# SCH.net
KiCad netlist of a schematic drawn in Altium Designer
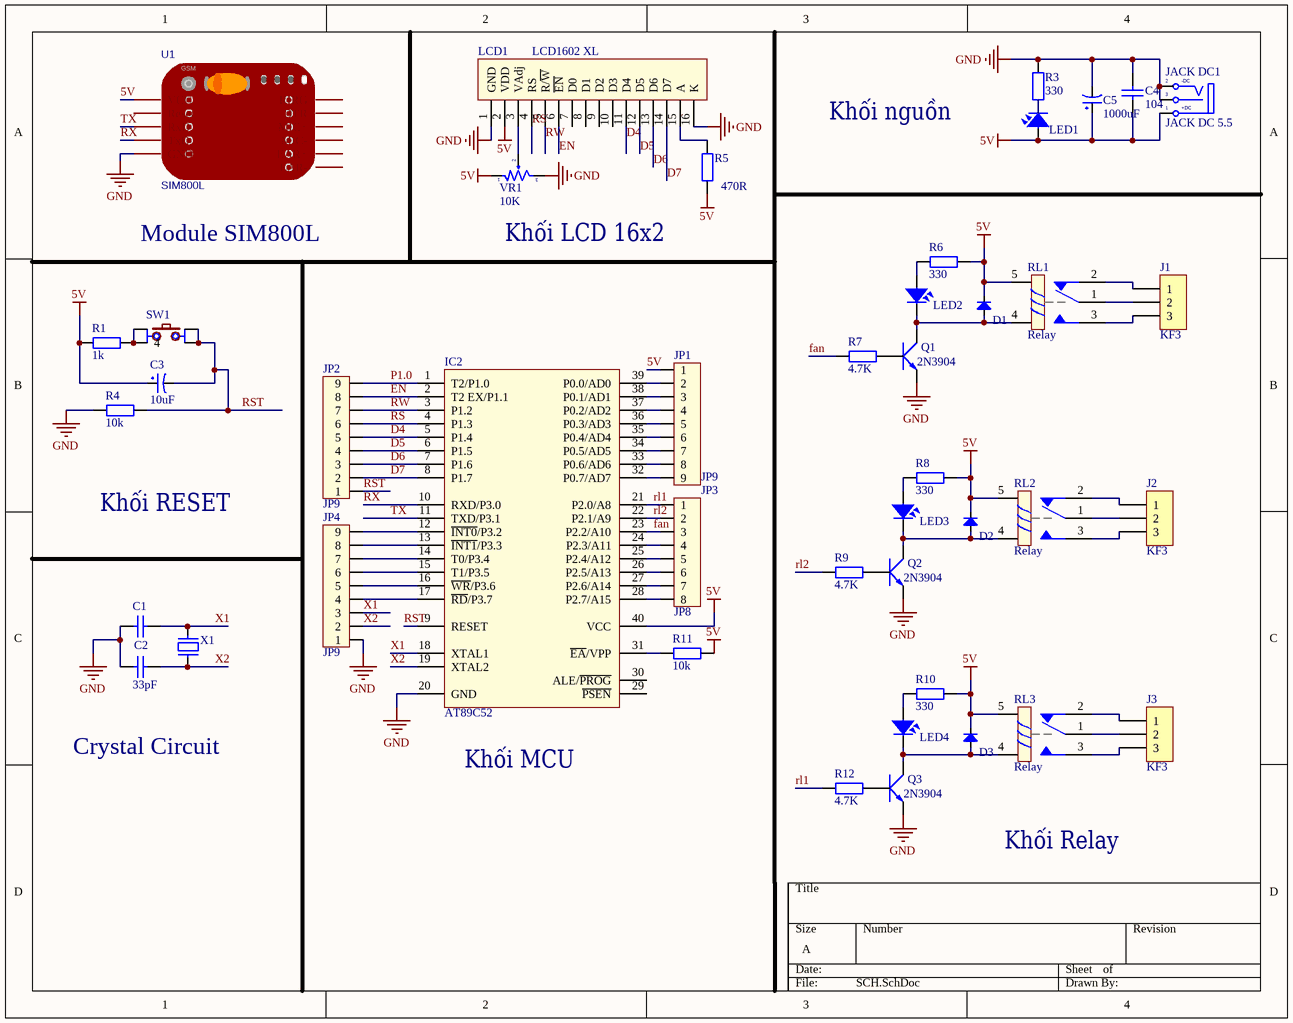
[diagram p0: SCH.SchDoc]

(export (version "E")
  (design (tool "Eeschema 10.0.6"))
  (components
    (comp (ref "C1")
      (value "30pF")
      (footprint "tu gom")
      (description "Cắm")
      (libsource (lib "Altium_Lib_by_KhueNguyenCreator") (part "Tu gom 30pF 50V"))
    )
    (comp (ref "C2")
      (value "33pF")
      (footprint "tu gom")
      (description "Cắm")
      (libsource (lib "Altium_Lib_by_KhueNguyenCreator") (part "Tu gom 30pF 50V"))
    )
    (comp (ref "C3")
      (value "10uF")
      (footprint "tu hoa 4mm")
      (description "Cắm")
      (libsource (lib "Altium_Lib_by_KhueNguyenCreator") (part "Tu Hoa 10uF 16V 4x7"))
    )
    (comp (ref "C4")
      (value "104")
      (footprint "tu gom")
      (description "Cắm")
      (libsource (lib "Altium_Lib_by_KhueNguyenCreator") (part "Tu gom 104 50V"))
    )
    (comp (ref "C5")
      (value "1000uF")
      (footprint "tu hoa 10mm")
      (description "Cắm")
      (libsource (lib "Altium_Lib_by_KhueNguyenCreator") (part "Tu Hoa 1000uF 10V 10x12"))
    )
    (comp (ref "D1")
      (value "Diode")
      (footprint "DIO-1A")
      (description "Default Diode")
      (fields (field (name "PUBLISHER") "Altium Limited"))
      (libsource (lib "TechMT.VN_Lib_Project v2") (part "Diode"))
    )
    (comp (ref "D2")
      (value "Diode")
      (footprint "DIO-1A")
      (description "Default Diode")
      (fields (field (name "PUBLISHER") "Altium Limited"))
      (libsource (lib "TechMT.VN_Lib_Project v2") (part "Diode"))
    )
    (comp (ref "D3")
      (value "Diode")
      (footprint "DIO-1A")
      (description "Default Diode")
      (fields (field (name "PUBLISHER") "Altium Limited"))
      (libsource (lib "TechMT.VN_Lib_Project v2") (part "Diode"))
    )
    (comp (ref "IC2")
      (value "AT89C52")
      (footprint "DIP40/W0.6")
      (description "Cắm")
      (libsource (lib "Altium_Lib_by_KhueNguyenCreator") (part "AT89C52"))
    )
    (comp (ref "J1")
      (value "KF3")
      (footprint "KF3-5.08")
      (fields
        (field (name "MANUFACTURER") "Würth Elektronik eiSos GmbH")
        (field (name "PARTNO") "691103110003")
        (field (name "CREATED BY") "Karrer Zheng")
      )
      (libsource (lib "TechMT.VN_Lib_Project v2") (part "KF3"))
    )
    (comp (ref "J2")
      (value "KF3")
      (footprint "KF3-5.08")
      (fields
        (field (name "MANUFACTURER") "Würth Elektronik eiSos GmbH")
        (field (name "PARTNO") "691103110003")
        (field (name "CREATED BY") "Karrer Zheng")
      )
      (libsource (lib "TechMT.VN_Lib_Project v2") (part "KF3"))
    )
    (comp (ref "J3")
      (value "KF3")
      (footprint "KF3-5.08")
      (fields
        (field (name "MANUFACTURER") "Würth Elektronik eiSos GmbH")
        (field (name "PARTNO") "691103110003")
        (field (name "CREATED BY") "Karrer Zheng")
      )
      (libsource (lib "TechMT.VN_Lib_Project v2") (part "KF3"))
    )
    (comp (ref "JACK DC1")
      (value "JACK DC 5.5")
      (footprint "JACK DC 5.5")
      (libsource (lib "Altium_Lib_by_KhueNguyenCreator") (part "JACK DC 5.5"))
    )
    (comp (ref "JP1")
      (value "JP9")
      (footprint "Header9")
      (description "Connector 9")
      (libsource (lib "") (part "Header9_1"))
    )
    (comp (ref "JP2")
      (value "JP9")
      (footprint "Header9")
      (description "Connector 9")
      (libsource (lib "TechMT.VN_Lib_Project v2") (part "Header9"))
    )
    (comp (ref "JP3")
      (value "JP8")
      (footprint "Header8")
      (description "Connector 8")
      (libsource (lib "TechMT.VN_Lib_Project v2") (part "Header8"))
    )
    (comp (ref "JP4")
      (value "JP9")
      (footprint "Header9")
      (description "Connector 9")
      (libsource (lib "TechMT.VN_Lib_Project v2") (part "Header9"))
    )
    (comp (ref "LCD1")
      (value "LCD1602 XL")
      (footprint "LCD1602 with Jump")
      (description "LCD 1602 Xanh Lá")
      (libsource (lib "Altium_Lib_by_KhueNguyenCreator") (part "LCD1602 XL"))
    )
    (comp (ref "LED1")
      (value "LED")
      (footprint "LED-5MM-RED")
      (description "LED Single colour Green and Red")
      (libsource (lib "TechMT.VN_Lib_Project v2") (part "LED"))
    )
    (comp (ref "LED2")
      (value "LED")
      (footprint "LED-5MM-RED")
      (description "LED Single colour Green and Red")
      (libsource (lib "TechMT.VN_Lib_Project v2") (part "LED"))
    )
    (comp (ref "LED3")
      (value "LED")
      (footprint "LED-5MM-RED")
      (description "LED Single colour Green and Red")
      (libsource (lib "TechMT.VN_Lib_Project v2") (part "LED"))
    )
    (comp (ref "LED4")
      (value "LED")
      (footprint "LED-5MM-RED")
      (description "LED Single colour Green and Red")
      (libsource (lib "TechMT.VN_Lib_Project v2") (part "LED"))
    )
    (comp (ref "Q1")
      (value "2N3904")
      (footprint "TO92-123")
      (description "NPN 600mW, ECB")
      (libsource (lib "TechMT.VN_Lib_Project v2") (part "2N904"))
    )
    (comp (ref "Q2")
      (value "2N3904")
      (footprint "TO92-123")
      (description "NPN 600mW, ECB")
      (libsource (lib "TechMT.VN_Lib_Project v2") (part "2N904"))
    )
    (comp (ref "Q3")
      (value "2N3904")
      (footprint "TO92-123")
      (description "NPN 600mW, ECB")
      (libsource (lib "TechMT.VN_Lib_Project v2") (part "2N904"))
    )
    (comp (ref "R1")
      (value "1k")
      (footprint "tro vach 1/4w")
      (description "Cắm")
      (libsource (lib "Altium_Lib_by_KhueNguyenCreator") (part "Tro Vach 1/4W 1% 10k"))
    )
    (comp (ref "R3")
      (value "330")
      (footprint "tro vach 1/4w")
      (description "Cắm")
      (libsource (lib "Altium_Lib_by_KhueNguyenCreator") (part "Tro Vach 1/4W 1% 10k"))
    )
    (comp (ref "R4")
      (value "10k")
      (footprint "tro vach 1/4w")
      (description "Cắm")
      (libsource (lib "Altium_Lib_by_KhueNguyenCreator") (part "Tro Vach 1/4W 1% 10k"))
    )
    (comp (ref "R5")
      (value "470R")
      (footprint "tro vach 1/4w")
      (description "Cắm")
      (libsource (lib "Altium_Lib_by_KhueNguyenCreator") (part "Tro Vach 1/4W 1% 10k"))
    )
    (comp (ref "R6")
      (value "330")
      (footprint "tro vach 1/4w")
      (description "Cắm")
      (libsource (lib "Altium_Lib_by_KhueNguyenCreator") (part "Tro Vach 1/4W 1% 10k"))
    )
    (comp (ref "R7")
      (value "4.7K")
      (footprint "tro vach 1/4w")
      (description "Cắm")
      (libsource (lib "Altium_Lib_by_KhueNguyenCreator") (part "Tro Vach 1/4W 1% 10k"))
    )
    (comp (ref "R8")
      (value "330")
      (footprint "tro vach 1/4w")
      (description "Cắm")
      (libsource (lib "Altium_Lib_by_KhueNguyenCreator") (part "Tro Vach 1/4W 1% 10k"))
    )
    (comp (ref "R9")
      (value "4.7K")
      (footprint "tro vach 1/4w")
      (description "Cắm")
      (libsource (lib "Altium_Lib_by_KhueNguyenCreator") (part "Tro Vach 1/4W 1% 10k"))
    )
    (comp (ref "R10")
      (value "330")
      (footprint "tro vach 1/4w")
      (description "Cắm")
      (libsource (lib "Altium_Lib_by_KhueNguyenCreator") (part "Tro Vach 1/4W 1% 10k"))
    )
    (comp (ref "R11")
      (value "10k")
      (footprint "tro vach 1/4w")
      (description "Cắm")
      (libsource (lib "Altium_Lib_by_KhueNguyenCreator") (part "Tro Vach 1/4W 1% 10k"))
    )
    (comp (ref "R12")
      (value "4.7K")
      (footprint "tro vach 1/4w")
      (description "Cắm")
      (libsource (lib "Altium_Lib_by_KhueNguyenCreator") (part "Tro Vach 1/4W 1% 10k"))
    )
    (comp (ref "RL1")
      (value "Relay")
      (footprint "Relay 5 Chan SRD")
      (description "Relay 5 Chan")
      (libsource (lib "Altium_Lib_by_KhueNguyenCreator") (part "Relay 5 Chan SRD"))
    )
    (comp (ref "RL2")
      (value "Relay")
      (footprint "Relay 5 Chan SRD")
      (description "Relay 5 Chan")
      (libsource (lib "Altium_Lib_by_KhueNguyenCreator") (part "Relay 5 Chan SRD"))
    )
    (comp (ref "RL3")
      (value "Relay")
      (footprint "Relay 5 Chan SRD")
      (description "Relay 5 Chan")
      (libsource (lib "Altium_Lib_by_KhueNguyenCreator") (part "Relay 5 Chan SRD"))
    )
    (comp (ref "SW1")
      (value "SW")
      (footprint "SW2-DIP")
      (description "Switch button 4 pin")
      (libsource (lib "TechMT.VN_Lib_Project v2") (part "SW4"))
    )
    (comp (ref "U1")
      (value "SIM800L")
      (footprint "SIM800L MODULE")
      (fields (field (name "BOM_SUPPLIER PART") "B01DLIJM2E") (field (name "CONTRIBUTOR") "trigui"))
      (libsource (lib "sim800l") (part "SIM800L"))
    )
    (comp (ref "VR1")
      (value "10K")
      (footprint "Bien Tro Volume Don")
      (description "Cắm")
      (libsource (lib "Altium_Lib_by_KhueNguyenCreator") (part "Triet Ap Don 10k"))
    )
    (comp (ref "X1")
      (value "11.0592Mhz")
      (footprint "XT2")
      (description "Crystal, 32.768 KHz, -40 to 85 degC, 3.2 x 1.5 x 0.9 mm SMD")
      (libsource (lib "TechMT.VN_Lib_Project v2") (part "XT2"))
    )
  )
  (nets
    (net (code "1") (name "/D4") (class "Default")
      (node (ref "IC2") (pin "5") (pinfunction "P1.4_5") (pintype "passive"))
      (node (ref "JP2") (pin "5") (pinfunction "5_5") (pintype "passive"))
      (node (ref "LCD1") (pin "11") (pinfunction "D4_11") (pintype "passive"))
    )
    (net (code "2") (name "/D5") (class "Default")
      (node (ref "IC2") (pin "6") (pinfunction "P1.5_6") (pintype "passive"))
      (node (ref "JP2") (pin "4") (pinfunction "4_4") (pintype "passive"))
      (node (ref "LCD1") (pin "12") (pinfunction "D5_12") (pintype "passive"))
    )
    (net (code "3") (name "/D6") (class "Default")
      (node (ref "IC2") (pin "7") (pinfunction "P1.6_7") (pintype "passive"))
      (node (ref "JP2") (pin "3") (pinfunction "3_3") (pintype "passive"))
      (node (ref "LCD1") (pin "13") (pinfunction "D6_13") (pintype "passive"))
    )
    (net (code "4") (name "/D7") (class "Default")
      (node (ref "IC2") (pin "8") (pinfunction "P1.7_8") (pintype "passive"))
      (node (ref "JP2") (pin "2") (pinfunction "2_2") (pintype "passive"))
      (node (ref "LCD1") (pin "14") (pinfunction "D7_14") (pintype "passive"))
    )
    (net (code "5") (name "/EN") (class "Default")
      (node (ref "IC2") (pin "2") (pinfunction "T2_EX/P1.1_2") (pintype "passive"))
      (node (ref "JP2") (pin "8") (pinfunction "8_8") (pintype "passive"))
      (node (ref "LCD1") (pin "6") (pinfunction "~{EN}_6") (pintype "passive"))
    )
    (net (code "6") (name "/P1.0") (class "Default")
      (node (ref "IC2") (pin "1") (pinfunction "T2/P1.0_1") (pintype "passive"))
      (node (ref "JP2") (pin "9") (pinfunction "9_9") (pintype "passive"))
    )
    (net (code "7") (name "/RS") (class "Default")
      (node (ref "IC2") (pin "4") (pinfunction "P1.3_4") (pintype "passive"))
      (node (ref "JP2") (pin "6") (pinfunction "6_6") (pintype "passive"))
      (node (ref "LCD1") (pin "4") (pinfunction "RS_4") (pintype "passive"))
    )
    (net (code "8") (name "/RST") (class "Default")
      (node (ref "C3") (pin "2") (pinfunction "2_2") (pintype "passive"))
      (node (ref "IC2") (pin "9") (pinfunction "RESET_9") (pintype "passive"))
      (node (ref "JP2") (pin "1") (pinfunction "1_1") (pintype "passive"))
      (node (ref "R4") (pin "2") (pinfunction "2_2") (pintype "passive"))
      (node (ref "SW1") (pin "2") (pinfunction "2_2") (pintype "passive"))
      (node (ref "SW1") (pin "3") (pinfunction "3_3") (pintype "passive"))
    )
    (net (code "9") (name "/RW") (class "Default")
      (node (ref "IC2") (pin "3") (pinfunction "P1.2_3") (pintype "passive"))
      (node (ref "JP2") (pin "7") (pinfunction "7_7") (pintype "passive"))
      (node (ref "LCD1") (pin "5") (pinfunction "R/~{W}_5") (pintype "passive"))
    )
    (net (code "10") (name "/RX") (class "Default")
      (node (ref "IC2") (pin "10") (pinfunction "RXD/P3.0_10") (pintype "passive"))
      (node (ref "U1") (pin "4") (pinfunction "TxD_4") (pintype "passive"))
    )
    (net (code "11") (name "/TX") (class "Default")
      (node (ref "IC2") (pin "11") (pinfunction "TXD/P3.1_11") (pintype "passive"))
      (node (ref "U1") (pin "3") (pinfunction "RxD_3") (pintype "passive"))
    )
    (net (code "12") (name "/X1") (class "Default")
      (node (ref "C1") (pin "1") (pinfunction "1_1") (pintype "passive"))
      (node (ref "IC2") (pin "18") (pinfunction "XTAL1_18") (pintype "passive"))
      (node (ref "JP4") (pin "3") (pinfunction "3_3") (pintype "passive"))
      (node (ref "X1") (pin "2") (pinfunction "2_2") (pintype "passive"))
    )
    (net (code "13") (name "/X2") (class "Default")
      (node (ref "C2") (pin "1") (pinfunction "1_1") (pintype "passive"))
      (node (ref "IC2") (pin "19") (pinfunction "XTAL2_19") (pintype "passive"))
      (node (ref "JP4") (pin "2") (pinfunction "2_2") (pintype "passive"))
      (node (ref "X1") (pin "1") (pinfunction "1_1") (pintype "passive"))
    )
    (net (code "14") (name "/fan") (class "Default")
      (node (ref "IC2") (pin "23") (pinfunction "P2.2/A10_23") (pintype "passive"))
      (node (ref "JP3") (pin "3") (pinfunction "3_3") (pintype "passive"))
      (node (ref "R7") (pin "1") (pinfunction "1_1") (pintype "passive"))
    )
    (net (code "15") (name "/rl1") (class "Default")
      (node (ref "IC2") (pin "21") (pinfunction "P2.0/A8_21") (pintype "passive"))
      (node (ref "JP3") (pin "1") (pinfunction "1_1") (pintype "passive"))
      (node (ref "R12") (pin "1") (pinfunction "1_1") (pintype "passive"))
    )
    (net (code "16") (name "/rl2") (class "Default")
      (node (ref "IC2") (pin "22") (pinfunction "P2.1/A9_22") (pintype "passive"))
      (node (ref "JP3") (pin "2") (pinfunction "2_2") (pintype "passive"))
      (node (ref "R9") (pin "1") (pinfunction "1_1") (pintype "passive"))
    )
    (net (code "17") (name "5V") (class "Default")
      (node (ref "C3") (pin "1") (pinfunction "1_1") (pintype "passive"))
      (node (ref "C4") (pin "2") (pinfunction "2_2") (pintype "passive"))
      (node (ref "C5") (pin "1") (pinfunction "1_1") (pintype "passive"))
      (node (ref "D1") (pin "2") (pinfunction "K_2") (pintype "passive"))
      (node (ref "D2") (pin "2") (pinfunction "K_2") (pintype "passive"))
      (node (ref "D3") (pin "2") (pinfunction "K_2") (pintype "passive"))
      (node (ref "IC2") (pin "40") (pinfunction "VCC_40") (pintype "power_in"))
      (node (ref "JACK DC1") (pin "1") (pinfunction "T_1") (pintype "passive"))
      (node (ref "JP1") (pin "1") (pinfunction "1_1") (pintype "passive"))
      (node (ref "LCD1") (pin "2") (pinfunction "VDD_2") (pintype "passive"))
      (node (ref "LED1") (pin "1") (pinfunction "1_1") (pintype "passive"))
      (node (ref "R1") (pin "1") (pinfunction "1_1") (pintype "passive"))
      (node (ref "R10") (pin "2") (pinfunction "2_2") (pintype "passive"))
      (node (ref "R11") (pin "2") (pinfunction "2_2") (pintype "passive"))
      (node (ref "R5") (pin "1") (pinfunction "1_1") (pintype "passive"))
      (node (ref "R6") (pin "2") (pinfunction "2_2") (pintype "passive"))
      (node (ref "R8") (pin "2") (pinfunction "2_2") (pintype "passive"))
      (node (ref "RL1") (pin "5") (pinfunction "5_5") (pintype "passive"))
      (node (ref "RL2") (pin "5") (pinfunction "5_5") (pintype "passive"))
      (node (ref "RL3") (pin "5") (pinfunction "5_5") (pintype "passive"))
      (node (ref "U1") (pin "1") (pinfunction "VCC_1") (pintype "passive"))
      (node (ref "VR1") (pin "1") (pinfunction "1_1") (pintype "passive"))
    )
    (net (code "18") (name "GND") (class "Default")
      (node (ref "C1") (pin "2") (pinfunction "2_2") (pintype "passive"))
      (node (ref "C2") (pin "2") (pinfunction "2_2") (pintype "passive"))
      (node (ref "C4") (pin "1") (pinfunction "1_1") (pintype "passive"))
      (node (ref "C5") (pin "2") (pinfunction "2_2") (pintype "passive"))
      (node (ref "IC2") (pin "20") (pinfunction "GND_20") (pintype "open_emitter"))
      (node (ref "JACK DC1") (pin "2") (pinfunction "TN_2") (pintype "passive"))
      (node (ref "JACK DC1") (pin "3") (pinfunction "S_3") (pintype "power_in"))
      (node (ref "JP4") (pin "1") (pinfunction "1_1") (pintype "passive"))
      (node (ref "LCD1") (pin "1") (pinfunction "GND_1") (pintype "passive"))
      (node (ref "LCD1") (pin "16") (pinfunction "K_16") (pintype "passive"))
      (node (ref "Q1") (pin "1") (pinfunction "E_1") (pintype "passive"))
      (node (ref "Q2") (pin "1") (pinfunction "E_1") (pintype "passive"))
      (node (ref "Q3") (pin "1") (pinfunction "E_1") (pintype "passive"))
      (node (ref "R3") (pin "2") (pinfunction "2_2") (pintype "passive"))
      (node (ref "R4") (pin "1") (pinfunction "1_1") (pintype "passive"))
      (node (ref "U1") (pin "5") (pinfunction "GND_5") (pintype "passive"))
      (node (ref "VR1") (pin "3") (pinfunction "3_3") (pintype "passive"))
    )
    (net (code "19") (name "Net-(D1-A)") (class "Default")
      (node (ref "D1") (pin "1") (pinfunction "A_1") (pintype "passive"))
      (node (ref "LED2") (pin "2") (pinfunction "2_2") (pintype "passive"))
      (node (ref "Q1") (pin "3") (pinfunction "C_3") (pintype "passive"))
      (node (ref "RL1") (pin "4") (pinfunction "4_4") (pintype "passive"))
    )
    (net (code "20") (name "Net-(D2-A)") (class "Default")
      (node (ref "D2") (pin "1") (pinfunction "A_1") (pintype "passive"))
      (node (ref "LED3") (pin "2") (pinfunction "2_2") (pintype "passive"))
      (node (ref "Q2") (pin "3") (pinfunction "C_3") (pintype "passive"))
      (node (ref "RL2") (pin "4") (pinfunction "4_4") (pintype "passive"))
    )
    (net (code "21") (name "Net-(D3-A)") (class "Default")
      (node (ref "D3") (pin "1") (pinfunction "A_1") (pintype "passive"))
      (node (ref "LED4") (pin "2") (pinfunction "2_2") (pintype "passive"))
      (node (ref "Q3") (pin "3") (pinfunction "C_3") (pintype "passive"))
      (node (ref "RL3") (pin "4") (pinfunction "4_4") (pintype "passive"))
    )
    (net (code "22") (name "Net-(IC2-P0.0{slash}AD0)") (class "Default")
      (node (ref "IC2") (pin "39") (pinfunction "P0.0/AD0_39") (pintype "passive"))
      (node (ref "JP1") (pin "2") (pinfunction "2_2") (pintype "passive"))
    )
    (net (code "23") (name "Net-(IC2-P0.1{slash}AD1)") (class "Default")
      (node (ref "IC2") (pin "38") (pinfunction "P0.1/AD1_38") (pintype "passive"))
      (node (ref "JP1") (pin "3") (pinfunction "3_3") (pintype "passive"))
    )
    (net (code "24") (name "Net-(IC2-P0.2{slash}AD2)") (class "Default")
      (node (ref "IC2") (pin "37") (pinfunction "P0.2/AD2_37") (pintype "passive"))
      (node (ref "JP1") (pin "4") (pinfunction "4_4") (pintype "passive"))
    )
    (net (code "25") (name "Net-(IC2-P0.3{slash}AD3)") (class "Default")
      (node (ref "IC2") (pin "36") (pinfunction "P0.3/AD3_36") (pintype "passive"))
      (node (ref "JP1") (pin "5") (pinfunction "5_5") (pintype "passive"))
    )
    (net (code "26") (name "Net-(IC2-P0.4{slash}AD4)") (class "Default")
      (node (ref "IC2") (pin "35") (pinfunction "P0.4/AD4_35") (pintype "passive"))
      (node (ref "JP1") (pin "6") (pinfunction "6_6") (pintype "passive"))
    )
    (net (code "27") (name "Net-(IC2-P0.5{slash}AD5)") (class "Default")
      (node (ref "IC2") (pin "34") (pinfunction "P0.5/AD5_34") (pintype "passive"))
      (node (ref "JP1") (pin "7") (pinfunction "7_7") (pintype "passive"))
    )
    (net (code "28") (name "Net-(IC2-P0.6{slash}AD6)") (class "Default")
      (node (ref "IC2") (pin "33") (pinfunction "P0.6/AD6_33") (pintype "passive"))
      (node (ref "JP1") (pin "8") (pinfunction "8_8") (pintype "passive"))
    )
    (net (code "29") (name "Net-(IC2-P0.7{slash}AD7)") (class "Default")
      (node (ref "IC2") (pin "32") (pinfunction "P0.7/AD7_32") (pintype "passive"))
      (node (ref "JP1") (pin "9") (pinfunction "9_9") (pintype "passive"))
    )
    (net (code "30") (name "Net-(IC2-P2.3{slash}A11)") (class "Default")
      (node (ref "IC2") (pin "24") (pinfunction "P2.3/A11_24") (pintype "passive"))
      (node (ref "JP3") (pin "4") (pinfunction "4_4") (pintype "passive"))
    )
    (net (code "31") (name "Net-(IC2-P2.4{slash}A12)") (class "Default")
      (node (ref "IC2") (pin "25") (pinfunction "P2.4/A12_25") (pintype "passive"))
      (node (ref "JP3") (pin "5") (pinfunction "5_5") (pintype "passive"))
    )
    (net (code "32") (name "Net-(IC2-P2.5{slash}A13)") (class "Default")
      (node (ref "IC2") (pin "26") (pinfunction "P2.5/A13_26") (pintype "passive"))
      (node (ref "JP3") (pin "6") (pinfunction "6_6") (pintype "passive"))
    )
    (net (code "33") (name "Net-(IC2-P2.6{slash}A14)") (class "Default")
      (node (ref "IC2") (pin "27") (pinfunction "P2.6/A14_27") (pintype "passive"))
      (node (ref "JP3") (pin "7") (pinfunction "7_7") (pintype "passive"))
    )
    (net (code "34") (name "Net-(IC2-P2.7{slash}A15)") (class "Default")
      (node (ref "IC2") (pin "28") (pinfunction "P2.7/A15_28") (pintype "passive"))
      (node (ref "JP3") (pin "8") (pinfunction "8_8") (pintype "passive"))
    )
    (net (code "35") (name "Net-(IC2-T0{slash}P3.4)") (class "Default")
      (node (ref "IC2") (pin "14") (pinfunction "T0/P3.4_14") (pintype "passive"))
      (node (ref "JP4") (pin "7") (pinfunction "7_7") (pintype "passive"))
    )
    (net (code "36") (name "Net-(IC2-T1{slash}P3.5)") (class "Default")
      (node (ref "IC2") (pin "15") (pinfunction "T1/P3.5_15") (pintype "passive"))
      (node (ref "JP4") (pin "6") (pinfunction "6_6") (pintype "passive"))
    )
    (net (code "37") (name "Net-(IC2-~{EA}{slash}VPP)") (class "Default")
      (node (ref "IC2") (pin "31") (pinfunction "~{EA}/VPP_31") (pintype "passive"))
      (node (ref "R11") (pin "1") (pinfunction "1_1") (pintype "passive"))
    )
    (net (code "38") (name "Net-(IC2-~{INT0}{slash}P3.2)") (class "Default")
      (node (ref "IC2") (pin "12") (pinfunction "~{INT0}/P3.2_12") (pintype "passive"))
      (node (ref "JP4") (pin "9") (pinfunction "9_9") (pintype "passive"))
    )
    (net (code "39") (name "Net-(IC2-~{INT1}{slash}P3.3)") (class "Default")
      (node (ref "IC2") (pin "13") (pinfunction "~{INT1}/P3.3_13") (pintype "passive"))
      (node (ref "JP4") (pin "8") (pinfunction "8_8") (pintype "passive"))
    )
    (net (code "40") (name "Net-(IC2-~{RD}{slash}P3.7)") (class "Default")
      (node (ref "IC2") (pin "17") (pinfunction "~{RD}/P3.7_17") (pintype "passive"))
      (node (ref "JP4") (pin "4") (pinfunction "4_4") (pintype "passive"))
    )
    (net (code "41") (name "Net-(IC2-~{WR}{slash}P3.6)") (class "Default")
      (node (ref "IC2") (pin "16") (pinfunction "~{WR}/P3.6_16") (pintype "passive"))
      (node (ref "JP4") (pin "5") (pinfunction "5_5") (pintype "passive"))
    )
    (net (code "42") (name "Net-(J1-Pad1)") (class "Default")
      (node (ref "J1") (pin "1") (pinfunction "1_1") (pintype "passive"))
      (node (ref "RL1") (pin "2") (pinfunction "2_2") (pintype "passive"))
    )
    (net (code "43") (name "Net-(J1-Pad2)") (class "Default")
      (node (ref "J1") (pin "2") (pinfunction "2_2") (pintype "passive"))
      (node (ref "RL1") (pin "1") (pinfunction "1_1") (pintype "passive"))
    )
    (net (code "44") (name "Net-(J1-Pad3)") (class "Default")
      (node (ref "J1") (pin "3") (pinfunction "3_3") (pintype "passive"))
      (node (ref "RL1") (pin "3") (pinfunction "3_3") (pintype "passive"))
    )
    (net (code "45") (name "Net-(J2-Pad1)") (class "Default")
      (node (ref "J2") (pin "1") (pinfunction "1_1") (pintype "passive"))
      (node (ref "RL2") (pin "2") (pinfunction "2_2") (pintype "passive"))
    )
    (net (code "46") (name "Net-(J2-Pad2)") (class "Default")
      (node (ref "J2") (pin "2") (pinfunction "2_2") (pintype "passive"))
      (node (ref "RL2") (pin "1") (pinfunction "1_1") (pintype "passive"))
    )
    (net (code "47") (name "Net-(J2-Pad3)") (class "Default")
      (node (ref "J2") (pin "3") (pinfunction "3_3") (pintype "passive"))
      (node (ref "RL2") (pin "3") (pinfunction "3_3") (pintype "passive"))
    )
    (net (code "48") (name "Net-(J3-Pad1)") (class "Default")
      (node (ref "J3") (pin "1") (pinfunction "1_1") (pintype "passive"))
      (node (ref "RL3") (pin "2") (pinfunction "2_2") (pintype "passive"))
    )
    (net (code "49") (name "Net-(J3-Pad2)") (class "Default")
      (node (ref "J3") (pin "2") (pinfunction "2_2") (pintype "passive"))
      (node (ref "RL3") (pin "1") (pinfunction "1_1") (pintype "passive"))
    )
    (net (code "50") (name "Net-(J3-Pad3)") (class "Default")
      (node (ref "J3") (pin "3") (pinfunction "3_3") (pintype "passive"))
      (node (ref "RL3") (pin "3") (pinfunction "3_3") (pintype "passive"))
    )
    (net (code "51") (name "Net-(LCD1-A)") (class "Default")
      (node (ref "LCD1") (pin "15") (pinfunction "A_15") (pintype "passive"))
      (node (ref "R5") (pin "2") (pinfunction "2_2") (pintype "passive"))
    )
    (net (code "52") (name "Net-(LCD1-VAdj)") (class "Default")
      (node (ref "LCD1") (pin "3") (pinfunction "VAdj_3") (pintype "passive"))
      (node (ref "VR1") (pin "2") (pinfunction "2_2") (pintype "passive"))
    )
    (net (code "53") (name "Net-(LED1-Pad2)") (class "Default")
      (node (ref "LED1") (pin "2") (pinfunction "2_2") (pintype "passive"))
      (node (ref "R3") (pin "1") (pinfunction "1_1") (pintype "passive"))
    )
    (net (code "54") (name "Net-(LED2-Pad1)") (class "Default")
      (node (ref "LED2") (pin "1") (pinfunction "1_1") (pintype "passive"))
      (node (ref "R6") (pin "1") (pinfunction "1_1") (pintype "passive"))
    )
    (net (code "55") (name "Net-(LED3-Pad1)") (class "Default")
      (node (ref "LED3") (pin "1") (pinfunction "1_1") (pintype "passive"))
      (node (ref "R8") (pin "1") (pinfunction "1_1") (pintype "passive"))
    )
    (net (code "56") (name "Net-(LED4-Pad1)") (class "Default")
      (node (ref "LED4") (pin "1") (pinfunction "1_1") (pintype "passive"))
      (node (ref "R10") (pin "1") (pinfunction "1_1") (pintype "passive"))
    )
    (net (code "57") (name "Net-(Q1-B)") (class "Default")
      (node (ref "Q1") (pin "2") (pinfunction "B_2") (pintype "passive"))
      (node (ref "R7") (pin "2") (pinfunction "2_2") (pintype "passive"))
    )
    (net (code "58") (name "Net-(Q2-B)") (class "Default")
      (node (ref "Q2") (pin "2") (pinfunction "B_2") (pintype "passive"))
      (node (ref "R9") (pin "2") (pinfunction "2_2") (pintype "passive"))
    )
    (net (code "59") (name "Net-(Q3-B)") (class "Default")
      (node (ref "Q3") (pin "2") (pinfunction "B_2") (pintype "passive"))
      (node (ref "R12") (pin "2") (pinfunction "2_2") (pintype "passive"))
    )
    (net (code "60") (name "Net-(R1-Pad2)") (class "Default")
      (node (ref "R1") (pin "2") (pinfunction "2_2") (pintype "passive"))
      (node (ref "SW1") (pin "1") (pintype "passive"))
      (node (ref "SW1") (pin "4") (pinfunction "4_4") (pintype "passive"))
    )
    (net (code "61") (name "unconnected-(IC2-ALE{slash}~{PROG}-Pad30)") (class "Default")
      (node (ref "IC2") (pin "30") (pinfunction "ALE/~{PROG}_30") (pintype "passive"))
    )
    (net (code "62") (name "unconnected-(IC2-~{PSEN}-Pad29)") (class "Default")
      (node (ref "IC2") (pin "29") (pinfunction "~{PSEN}_29") (pintype "passive"))
    )
    (net (code "63") (name "unconnected-(LCD1-D0-Pad7)") (class "Default")
      (node (ref "LCD1") (pin "7") (pinfunction "D0_7") (pintype "passive"))
    )
    (net (code "64") (name "unconnected-(LCD1-D1-Pad8)") (class "Default")
      (node (ref "LCD1") (pin "8") (pinfunction "D1_8") (pintype "passive"))
    )
    (net (code "65") (name "unconnected-(LCD1-D2-Pad9)") (class "Default")
      (node (ref "LCD1") (pin "9") (pinfunction "D2_9") (pintype "passive"))
    )
    (net (code "66") (name "unconnected-(LCD1-D3-Pad10)") (class "Default")
      (node (ref "LCD1") (pin "10") (pinfunction "D3_10") (pintype "passive"))
    )
    (net (code "67") (name "unconnected-(U1-DTR-Pad7)") (class "Default")
      (node (ref "U1") (pin "7") (pinfunction "DTR_7") (pintype "passive"))
    )
    (net (code "68") (name "unconnected-(U1-EAR+-Pad10)") (class "Default")
      (node (ref "U1") (pin "10") (pinfunction "EAR+_10") (pintype "passive"))
    )
    (net (code "69") (name "unconnected-(U1-EAR--Pad11)") (class "Default")
      (node (ref "U1") (pin "11") (pinfunction "EAR-_11") (pintype "passive"))
    )
    (net (code "70") (name "unconnected-(U1-MIC+-Pad8)") (class "Default")
      (node (ref "U1") (pin "8") (pinfunction "MIC+_8") (pintype "passive"))
    )
    (net (code "71") (name "unconnected-(U1-MIC--Pad9)") (class "Default")
      (node (ref "U1") (pin "9") (pinfunction "MIC-_9") (pintype "passive"))
    )
    (net (code "72") (name "unconnected-(U1-RIRG-Pad6)") (class "Default")
      (node (ref "U1") (pin "6") (pinfunction "RIRG_6") (pintype "passive"))
    )
    (net (code "73") (name "unconnected-(U1-Reset-Pad2)") (class "Default")
      (node (ref "U1") (pin "2") (pinfunction "Reset_2") (pintype "passive"))
    )
  )
)
